# SCH_B_Register_2021-10-13.net
KiCad netlist of a schematic drawn in EasyEDA
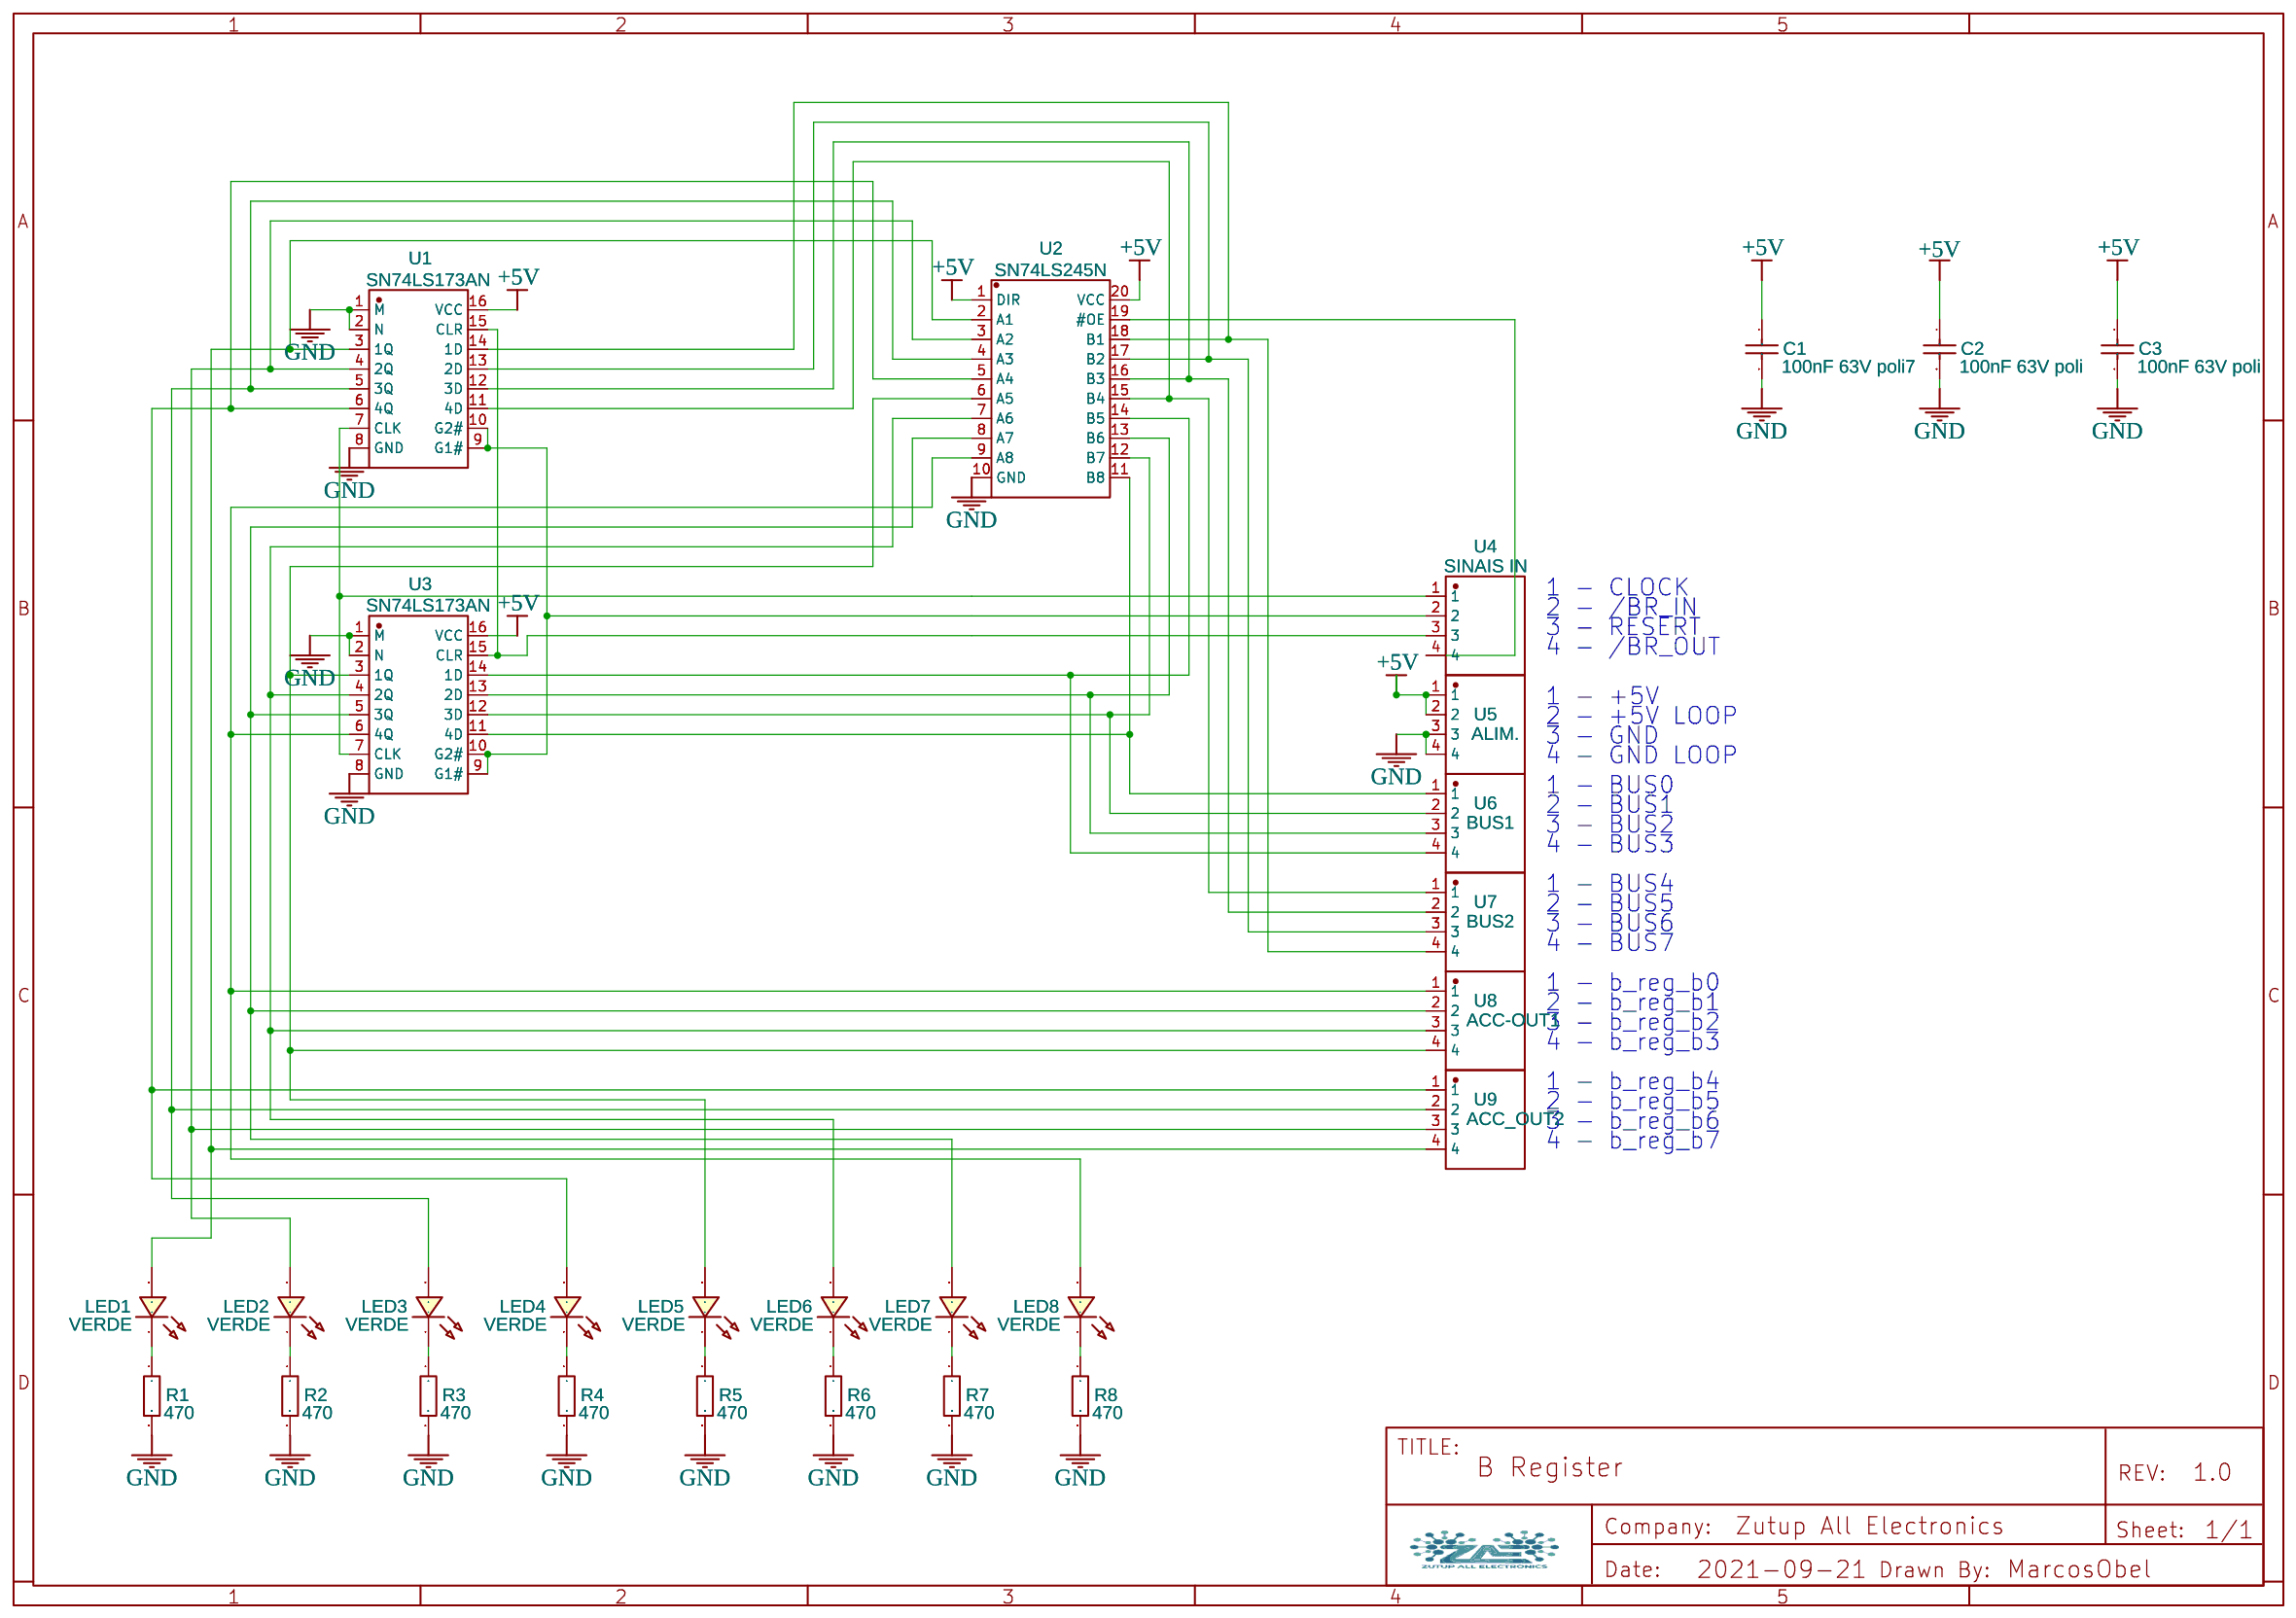
[diagram p0: schematic sheet]

(export (version "E")
  (design (tool "Eeschema 10.0.6"))
  (components
    (comp (ref "C1")
      (value "100nF 63V poli7")
      (fields
        (field (name "BOM_Manufacturer Part") "SR305C105KAR")
        (field (name "BOM_Supplier Part") "C444741")
      )
      (libsource (lib "") (part "SR305C105KAR"))
    )
    (comp (ref "C2")
      (value "100nF 63V poli")
      (fields
        (field (name "BOM_Manufacturer Part") "SR305C105KAR")
        (field (name "BOM_Supplier Part") "C444741")
      )
      (libsource (lib "") (part "SR305C105KAR"))
    )
    (comp (ref "C3")
      (value "100nF 63V poli")
      (fields
        (field (name "BOM_Manufacturer Part") "SR305C105KAR")
        (field (name "BOM_Supplier Part") "C444741")
      )
      (libsource (lib "") (part "SR305C105KAR"))
    )
    (comp (ref "LED1")
      (value "VERDE")
      (fields (field (name "BOM_Manufacturer Part") "264-7GD") (field (name "BOM_Supplier Part") "C605465"))
      (libsource (lib "") (part "264-7GD"))
    )
    (comp (ref "LED2")
      (value "VERDE")
      (fields (field (name "BOM_Manufacturer Part") "264-7GD") (field (name "BOM_Supplier Part") "C605465"))
      (libsource (lib "") (part "264-7GD"))
    )
    (comp (ref "LED3")
      (value "VERDE")
      (fields (field (name "BOM_Manufacturer Part") "264-7GD") (field (name "BOM_Supplier Part") "C605465"))
      (libsource (lib "") (part "264-7GD"))
    )
    (comp (ref "LED4")
      (value "VERDE")
      (fields (field (name "BOM_Manufacturer Part") "264-7GD") (field (name "BOM_Supplier Part") "C605465"))
      (libsource (lib "") (part "264-7GD"))
    )
    (comp (ref "LED5")
      (value "VERDE")
      (fields (field (name "BOM_Manufacturer Part") "264-7GD") (field (name "BOM_Supplier Part") "C605465"))
      (libsource (lib "") (part "264-7GD"))
    )
    (comp (ref "LED6")
      (value "VERDE")
      (fields (field (name "BOM_Manufacturer Part") "264-7GD") (field (name "BOM_Supplier Part") "C605465"))
      (libsource (lib "") (part "264-7GD"))
    )
    (comp (ref "LED7")
      (value "VERDE")
      (fields (field (name "BOM_Manufacturer Part") "264-7GD") (field (name "BOM_Supplier Part") "C605465"))
      (libsource (lib "") (part "264-7GD"))
    )
    (comp (ref "LED8")
      (value "VERDE")
      (fields (field (name "BOM_Manufacturer Part") "264-7GD") (field (name "BOM_Supplier Part") "C605465"))
      (libsource (lib "") (part "264-7GD"))
    )
    (comp (ref "R1")
      (value "470")
      (fields
        (field (name "BOM_Manufacturer Part") "CFR02SJ0823A10")
        (field (name "BOM_Supplier Part") "C69876")
      )
      (libsource (lib "") (part "CFR02SJ0823A10"))
    )
    (comp (ref "R2")
      (value "470")
      (fields
        (field (name "BOM_Manufacturer Part") "CFR02SJ0823A10")
        (field (name "BOM_Supplier Part") "C69876")
      )
      (libsource (lib "") (part "CFR02SJ0823A10"))
    )
    (comp (ref "R3")
      (value "470")
      (fields
        (field (name "BOM_Manufacturer Part") "CFR02SJ0823A10")
        (field (name "BOM_Supplier Part") "C69876")
      )
      (libsource (lib "") (part "CFR02SJ0823A10"))
    )
    (comp (ref "R4")
      (value "470")
      (fields
        (field (name "BOM_Manufacturer Part") "CFR02SJ0823A10")
        (field (name "BOM_Supplier Part") "C69876")
      )
      (libsource (lib "") (part "CFR02SJ0823A10"))
    )
    (comp (ref "R5")
      (value "470")
      (fields
        (field (name "BOM_Manufacturer Part") "CFR02SJ0823A10")
        (field (name "BOM_Supplier Part") "C69876")
      )
      (libsource (lib "") (part "CFR02SJ0823A10"))
    )
    (comp (ref "R6")
      (value "470")
      (fields
        (field (name "BOM_Manufacturer Part") "CFR02SJ0823A10")
        (field (name "BOM_Supplier Part") "C69876")
      )
      (libsource (lib "") (part "CFR02SJ0823A10"))
    )
    (comp (ref "R7")
      (value "470")
      (fields
        (field (name "BOM_Manufacturer Part") "CFR02SJ0823A10")
        (field (name "BOM_Supplier Part") "C69876")
      )
      (libsource (lib "") (part "CFR02SJ0823A10"))
    )
    (comp (ref "R8")
      (value "470")
      (fields
        (field (name "BOM_Manufacturer Part") "CFR02SJ0823A10")
        (field (name "BOM_Supplier Part") "C69876")
      )
      (libsource (lib "") (part "CFR02SJ0823A10"))
    )
    (comp (ref "U1")
      (value "SN74LS173AN")
      (fields (field (name "BOM_Supplier Part") "C1550125"))
      (libsource (lib "") (part "SN74LS173AN"))
    )
    (comp (ref "U2")
      (value "SN74LS245N")
      (fields (field (name "BOM_Supplier Part") "C352966"))
      (libsource (lib "") (part "SN74LS245N"))
    )
    (comp (ref "U3")
      (value "SN74LS173AN")
      (fields (field (name "BOM_Supplier Part") "C1550125"))
      (libsource (lib "") (part "SN74LS173AN"))
    )
    (comp (ref "U4")
      (value "SINAIS IN")
      (fields (field (name "BOM_Manufacturer Part") "171825-4") (field (name "BOM_Supplier Part") "C210162"))
      (libsource (lib "") (part "171825-4"))
    )
    (comp (ref "U5")
      (value "ALIM.")
      (fields (field (name "BOM_Manufacturer Part") "171825-4") (field (name "BOM_Supplier Part") "C210162"))
      (libsource (lib "") (part "171825-4"))
    )
    (comp (ref "U6")
      (value "BUS1")
      (fields (field (name "BOM_Manufacturer Part") "171825-4") (field (name "BOM_Supplier Part") "C210162"))
      (libsource (lib "") (part "171825-4"))
    )
    (comp (ref "U7")
      (value "BUS2")
      (fields (field (name "BOM_Manufacturer Part") "171825-4") (field (name "BOM_Supplier Part") "C210162"))
      (libsource (lib "") (part "171825-4"))
    )
    (comp (ref "U8")
      (value "ACC-OUT1")
      (fields (field (name "BOM_Manufacturer Part") "171825-4") (field (name "BOM_Supplier Part") "C210162"))
      (libsource (lib "") (part "171825-4"))
    )
    (comp (ref "U9")
      (value "ACC_OUT2")
      (fields (field (name "BOM_Manufacturer Part") "171825-4") (field (name "BOM_Supplier Part") "C210162"))
      (libsource (lib "") (part "171825-4"))
    )
  )
  (nets
    (net (code "1") (name "+5V") (class "Default")
      (node (ref "C1") (pin "1") (pinfunction "1_1") (pintype "input"))
      (node (ref "C2") (pin "1") (pinfunction "1_1") (pintype "input"))
      (node (ref "C3") (pin "1") (pinfunction "1_1") (pintype "input"))
      (node (ref "U1") (pin "16") (pinfunction "VCC_16") (pintype "unspecified"))
      (node (ref "U2") (pin "1") (pinfunction "DIR_1") (pintype "unspecified"))
      (node (ref "U2") (pin "20") (pinfunction "VCC_20") (pintype "unspecified"))
      (node (ref "U3") (pin "16") (pinfunction "VCC_16") (pintype "unspecified"))
      (node (ref "U5") (pin "1") (pinfunction "1_1") (pintype "unspecified"))
      (node (ref "U5") (pin "2") (pinfunction "2_2") (pintype "unspecified"))
    )
    (net (code "2") (name "GND") (class "Default")
      (node (ref "C1") (pin "2") (pinfunction "2_2") (pintype "input"))
      (node (ref "C2") (pin "2") (pinfunction "2_2") (pintype "input"))
      (node (ref "C3") (pin "2") (pinfunction "2_2") (pintype "input"))
      (node (ref "R1") (pin "2") (pinfunction "2_2") (pintype "input"))
      (node (ref "R2") (pin "2") (pinfunction "2_2") (pintype "input"))
      (node (ref "R3") (pin "2") (pinfunction "2_2") (pintype "input"))
      (node (ref "R4") (pin "2") (pinfunction "2_2") (pintype "input"))
      (node (ref "R5") (pin "2") (pinfunction "2_2") (pintype "input"))
      (node (ref "R6") (pin "2") (pinfunction "2_2") (pintype "input"))
      (node (ref "R7") (pin "2") (pinfunction "2_2") (pintype "input"))
      (node (ref "R8") (pin "2") (pinfunction "2_2") (pintype "input"))
      (node (ref "U1") (pin "1") (pinfunction "M_1") (pintype "unspecified"))
      (node (ref "U1") (pin "2") (pinfunction "N_2") (pintype "unspecified"))
      (node (ref "U1") (pin "8") (pinfunction "GND_8") (pintype "unspecified"))
      (node (ref "U2") (pin "10") (pinfunction "GND_10") (pintype "unspecified"))
      (node (ref "U3") (pin "1") (pinfunction "M_1") (pintype "unspecified"))
      (node (ref "U3") (pin "2") (pinfunction "N_2") (pintype "unspecified"))
      (node (ref "U3") (pin "8") (pinfunction "GND_8") (pintype "unspecified"))
      (node (ref "U5") (pin "3") (pinfunction "3_3") (pintype "unspecified"))
      (node (ref "U5") (pin "4") (pinfunction "4_4") (pintype "unspecified"))
    )
    (net (code "3") (name "Net-(LED1-+)") (class "Default")
      (node (ref "LED1") (pin "2") (pinfunction "+_2") (pintype "unspecified"))
      (node (ref "U1") (pin "3") (pinfunction "1Q_3") (pintype "unspecified"))
      (node (ref "U2") (pin "2") (pinfunction "A1_2") (pintype "unspecified"))
      (node (ref "U9") (pin "4") (pinfunction "4_4") (pintype "unspecified"))
    )
    (net (code "4") (name "Net-(LED1--)") (class "Default")
      (node (ref "LED1") (pin "1") (pinfunction "-_1") (pintype "unspecified"))
      (node (ref "R1") (pin "1") (pinfunction "1_1") (pintype "input"))
    )
    (net (code "5") (name "Net-(LED2-+)") (class "Default")
      (node (ref "LED2") (pin "2") (pinfunction "+_2") (pintype "unspecified"))
      (node (ref "U1") (pin "4") (pinfunction "2Q_4") (pintype "unspecified"))
      (node (ref "U2") (pin "3") (pinfunction "A2_3") (pintype "unspecified"))
      (node (ref "U9") (pin "3") (pinfunction "3_3") (pintype "unspecified"))
    )
    (net (code "6") (name "Net-(LED2--)") (class "Default")
      (node (ref "LED2") (pin "1") (pinfunction "-_1") (pintype "unspecified"))
      (node (ref "R2") (pin "1") (pinfunction "1_1") (pintype "input"))
    )
    (net (code "7") (name "Net-(LED3-+)") (class "Default")
      (node (ref "LED3") (pin "2") (pinfunction "+_2") (pintype "unspecified"))
      (node (ref "U1") (pin "5") (pinfunction "3Q_5") (pintype "unspecified"))
      (node (ref "U2") (pin "4") (pinfunction "A3_4") (pintype "unspecified"))
      (node (ref "U9") (pin "2") (pinfunction "2_2") (pintype "unspecified"))
    )
    (net (code "8") (name "Net-(LED3--)") (class "Default")
      (node (ref "LED3") (pin "1") (pinfunction "-_1") (pintype "unspecified"))
      (node (ref "R3") (pin "1") (pinfunction "1_1") (pintype "input"))
    )
    (net (code "9") (name "Net-(LED4-+)") (class "Default")
      (node (ref "LED4") (pin "2") (pinfunction "+_2") (pintype "unspecified"))
      (node (ref "U1") (pin "6") (pinfunction "4Q_6") (pintype "unspecified"))
      (node (ref "U2") (pin "5") (pinfunction "A4_5") (pintype "unspecified"))
      (node (ref "U9") (pin "1") (pinfunction "1_1") (pintype "unspecified"))
    )
    (net (code "10") (name "Net-(LED4--)") (class "Default")
      (node (ref "LED4") (pin "1") (pinfunction "-_1") (pintype "unspecified"))
      (node (ref "R4") (pin "1") (pinfunction "1_1") (pintype "input"))
    )
    (net (code "11") (name "Net-(LED5-+)") (class "Default")
      (node (ref "LED5") (pin "2") (pinfunction "+_2") (pintype "unspecified"))
      (node (ref "U2") (pin "6") (pinfunction "A5_6") (pintype "unspecified"))
      (node (ref "U3") (pin "3") (pinfunction "1Q_3") (pintype "unspecified"))
      (node (ref "U8") (pin "4") (pinfunction "4_4") (pintype "unspecified"))
    )
    (net (code "12") (name "Net-(LED5--)") (class "Default")
      (node (ref "LED5") (pin "1") (pinfunction "-_1") (pintype "unspecified"))
      (node (ref "R5") (pin "1") (pinfunction "1_1") (pintype "input"))
    )
    (net (code "13") (name "Net-(LED6-+)") (class "Default")
      (node (ref "LED6") (pin "2") (pinfunction "+_2") (pintype "unspecified"))
      (node (ref "U2") (pin "7") (pinfunction "A6_7") (pintype "unspecified"))
      (node (ref "U3") (pin "4") (pinfunction "2Q_4") (pintype "unspecified"))
      (node (ref "U8") (pin "3") (pinfunction "3_3") (pintype "unspecified"))
    )
    (net (code "14") (name "Net-(LED6--)") (class "Default")
      (node (ref "LED6") (pin "1") (pinfunction "-_1") (pintype "unspecified"))
      (node (ref "R6") (pin "1") (pinfunction "1_1") (pintype "input"))
    )
    (net (code "15") (name "Net-(LED7-+)") (class "Default")
      (node (ref "LED7") (pin "2") (pinfunction "+_2") (pintype "unspecified"))
      (node (ref "U2") (pin "8") (pinfunction "A7_8") (pintype "unspecified"))
      (node (ref "U3") (pin "5") (pinfunction "3Q_5") (pintype "unspecified"))
      (node (ref "U8") (pin "2") (pinfunction "2_2") (pintype "unspecified"))
    )
    (net (code "16") (name "Net-(LED7--)") (class "Default")
      (node (ref "LED7") (pin "1") (pinfunction "-_1") (pintype "unspecified"))
      (node (ref "R7") (pin "1") (pinfunction "1_1") (pintype "input"))
    )
    (net (code "17") (name "Net-(LED8-+)") (class "Default")
      (node (ref "LED8") (pin "2") (pinfunction "+_2") (pintype "unspecified"))
      (node (ref "U2") (pin "9") (pinfunction "A8_9") (pintype "unspecified"))
      (node (ref "U3") (pin "6") (pinfunction "4Q_6") (pintype "unspecified"))
      (node (ref "U8") (pin "1") (pinfunction "1_1") (pintype "unspecified"))
    )
    (net (code "18") (name "Net-(LED8--)") (class "Default")
      (node (ref "LED8") (pin "1") (pinfunction "-_1") (pintype "unspecified"))
      (node (ref "R8") (pin "1") (pinfunction "1_1") (pintype "input"))
    )
    (net (code "19") (name "Net-(U1-1D)") (class "Default")
      (node (ref "U1") (pin "14") (pinfunction "1D_14") (pintype "unspecified"))
      (node (ref "U2") (pin "18") (pinfunction "B1_18") (pintype "unspecified"))
      (node (ref "U7") (pin "4") (pinfunction "4_4") (pintype "unspecified"))
    )
    (net (code "20") (name "Net-(U1-2D)") (class "Default")
      (node (ref "U1") (pin "13") (pinfunction "2D_13") (pintype "unspecified"))
      (node (ref "U2") (pin "17") (pinfunction "B2_17") (pintype "unspecified"))
      (node (ref "U7") (pin "3") (pinfunction "3_3") (pintype "unspecified"))
    )
    (net (code "21") (name "Net-(U1-3D)") (class "Default")
      (node (ref "U1") (pin "12") (pinfunction "3D_12") (pintype "unspecified"))
      (node (ref "U2") (pin "16") (pinfunction "B3_16") (pintype "unspecified"))
      (node (ref "U7") (pin "2") (pinfunction "2_2") (pintype "unspecified"))
    )
    (net (code "22") (name "Net-(U1-4D)") (class "Default")
      (node (ref "U1") (pin "11") (pinfunction "4D_11") (pintype "unspecified"))
      (node (ref "U2") (pin "15") (pinfunction "B4_15") (pintype "unspecified"))
      (node (ref "U7") (pin "1") (pinfunction "1_1") (pintype "unspecified"))
    )
    (net (code "23") (name "Net-(U1-CLK)") (class "Default")
      (node (ref "U1") (pin "7") (pinfunction "CLK_7") (pintype "unspecified"))
      (node (ref "U3") (pin "7") (pinfunction "CLK_7") (pintype "unspecified"))
      (node (ref "U4") (pin "1") (pinfunction "1_1") (pintype "unspecified"))
    )
    (net (code "24") (name "Net-(U1-CLR)") (class "Default")
      (node (ref "U1") (pin "15") (pinfunction "CLR_15") (pintype "unspecified"))
      (node (ref "U3") (pin "15") (pinfunction "CLR_15") (pintype "unspecified"))
      (node (ref "U4") (pin "3") (pinfunction "3_3") (pintype "unspecified"))
    )
    (net (code "25") (name "Net-(U1-G1#)") (class "Default")
      (node (ref "U1") (pin "10") (pinfunction "G2#_10") (pintype "unspecified"))
      (node (ref "U1") (pin "9") (pinfunction "G1#_9") (pintype "unspecified"))
      (node (ref "U3") (pin "10") (pinfunction "G2#_10") (pintype "unspecified"))
      (node (ref "U3") (pin "9") (pinfunction "G1#_9") (pintype "unspecified"))
      (node (ref "U4") (pin "2") (pinfunction "2_2") (pintype "unspecified"))
    )
    (net (code "26") (name "Net-(U2-#OE)") (class "Default")
      (node (ref "U2") (pin "19") (pinfunction "#OE_19") (pintype "unspecified"))
      (node (ref "U4") (pin "4") (pinfunction "4_4") (pintype "unspecified"))
    )
    (net (code "27") (name "Net-(U2-B5)") (class "Default")
      (node (ref "U2") (pin "14") (pinfunction "B5_14") (pintype "unspecified"))
      (node (ref "U3") (pin "14") (pinfunction "1D_14") (pintype "unspecified"))
      (node (ref "U6") (pin "4") (pinfunction "4_4") (pintype "unspecified"))
    )
    (net (code "28") (name "Net-(U2-B6)") (class "Default")
      (node (ref "U2") (pin "13") (pinfunction "B6_13") (pintype "unspecified"))
      (node (ref "U3") (pin "13") (pinfunction "2D_13") (pintype "unspecified"))
      (node (ref "U6") (pin "3") (pinfunction "3_3") (pintype "unspecified"))
    )
    (net (code "29") (name "Net-(U2-B7)") (class "Default")
      (node (ref "U2") (pin "12") (pinfunction "B7_12") (pintype "unspecified"))
      (node (ref "U3") (pin "12") (pinfunction "3D_12") (pintype "unspecified"))
      (node (ref "U6") (pin "2") (pinfunction "2_2") (pintype "unspecified"))
    )
    (net (code "30") (name "Net-(U2-B8)") (class "Default")
      (node (ref "U2") (pin "11") (pinfunction "B8_11") (pintype "unspecified"))
      (node (ref "U3") (pin "11") (pinfunction "4D_11") (pintype "unspecified"))
      (node (ref "U6") (pin "1") (pinfunction "1_1") (pintype "unspecified"))
    )
  )
)
